# MCU063A_GPIO.net
KiCad netlist of a schematic drawn in Altium Designer
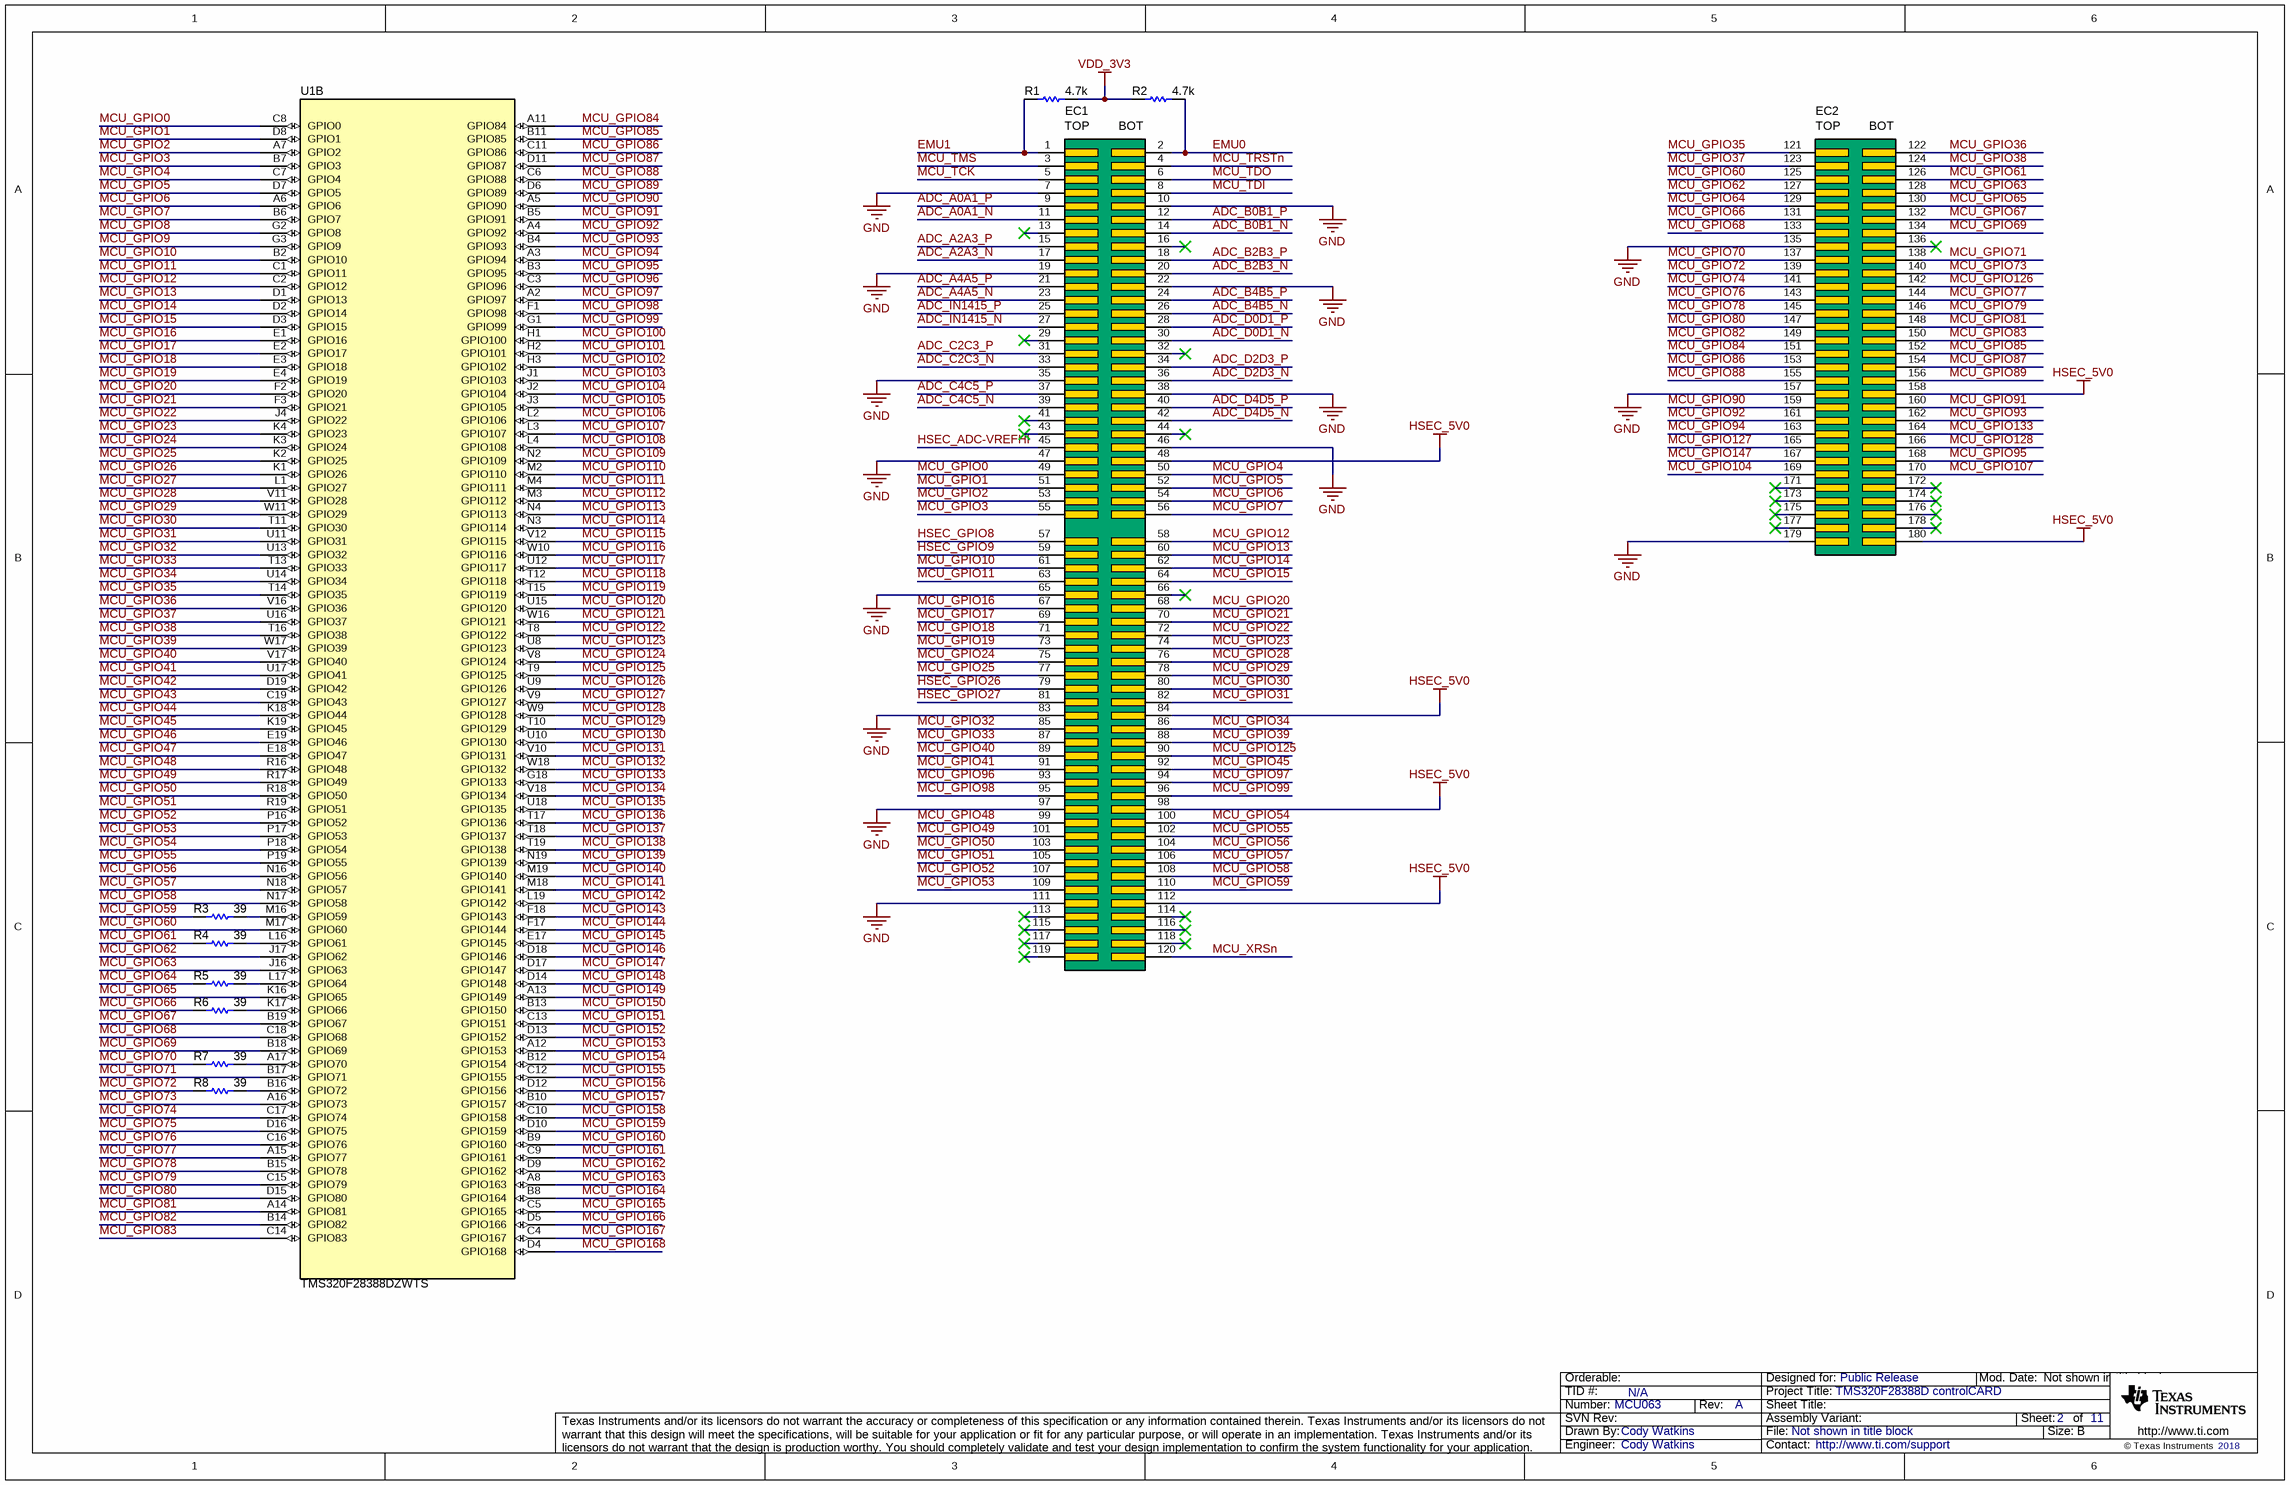
[diagram p0: MCU063A_GPIO.SchDoc]

(export (version "E")
  (design (tool "Eeschema 10.0.6"))
  (components
    (comp (ref "EC1")
      (value "controlCARD-120HSEC_Edge")
      (footprint "controlCARD-120HSEC_Edge")
      (description "C2000 controlCARD-120HSEC Edge Connector for Samtec HSEC8-160-01-L-DV-A-BL")
      (fields (field (name "MANUFACTURER") "Any"))
      (libsource (lib "Altium Vault - TI") (part "controlCARD-120HSEC_Edge"))
    )
    (comp (ref "EC2")
      (value "controlCARD-180HSEC-60pinAddon_Edge")
      (footprint "controlCARD-180HSEC-60pinAddon_Edge")
      (description "C2000 controlCARD-180HSEC (60-pin addon) Edge connector for Samtec HSEC8-130-01-L-DV-A")
      (fields (field (name "MANUFACTURER") "Any"))
      (libsource (lib "Altium Vault - TI") (part "controlCARD-180HSEC-60pinAddon_Edge"))
    )
    (comp (ref "R1")
      (value "CRCW04024K70JNED")
      (footprint "0402")
      (description "RES, 4.7 k, 5%, 0.063 W, AEC-Q200 Grade 0, 0402")
      (fields (field (name "MANUFACTURER") "Vishay-Dale") (field (name "VALUEDISPLAYED") "4.7k"))
      (libsource (lib "Altium Vault - TI") (part "Resistor"))
    )
    (comp (ref "R2")
      (value "CRCW04024K70JNED")
      (footprint "0402")
      (description "RES, 4.7 k, 5%, 0.063 W, AEC-Q200 Grade 0, 0402")
      (fields (field (name "MANUFACTURER") "Vishay-Dale") (field (name "VALUEDISPLAYED") "4.7k"))
      (libsource (lib "Altium Vault - TI") (part "Resistor"))
    )
    (comp (ref "R3")
      (value "CRCW040239R0JNED")
      (footprint "0402")
      (description "RES, 39, 5%, 0.063 W, AEC-Q200 Grade 0, 0402")
      (fields (field (name "MANUFACTURER") "Vishay-Dale") (field (name "VALUEDISPLAYED") "39"))
      (libsource (lib "Altium Vault - TI") (part "Resistor"))
    )
    (comp (ref "R4")
      (value "CRCW040239R0JNED")
      (footprint "0402")
      (description "RES, 39, 5%, 0.063 W, AEC-Q200 Grade 0, 0402")
      (fields (field (name "MANUFACTURER") "Vishay-Dale") (field (name "VALUEDISPLAYED") "39"))
      (libsource (lib "Altium Vault - TI") (part "Resistor"))
    )
    (comp (ref "R5")
      (value "CRCW040239R0JNED")
      (footprint "0402")
      (description "RES, 39, 5%, 0.063 W, AEC-Q200 Grade 0, 0402")
      (fields (field (name "MANUFACTURER") "Vishay-Dale") (field (name "VALUEDISPLAYED") "39"))
      (libsource (lib "Altium Vault - TI") (part "Resistor"))
    )
    (comp (ref "R6")
      (value "CRCW040239R0JNED")
      (footprint "0402")
      (description "RES, 39, 5%, 0.063 W, AEC-Q200 Grade 0, 0402")
      (fields (field (name "MANUFACTURER") "Vishay-Dale") (field (name "VALUEDISPLAYED") "39"))
      (libsource (lib "Altium Vault - TI") (part "Resistor"))
    )
    (comp (ref "R7")
      (value "CRCW040239R0JNED")
      (footprint "0402")
      (description "RES, 39, 5%, 0.063 W, AEC-Q200 Grade 0, 0402")
      (fields (field (name "MANUFACTURER") "Vishay-Dale") (field (name "VALUEDISPLAYED") "39"))
      (libsource (lib "Altium Vault - TI") (part "Resistor"))
    )
    (comp (ref "R8")
      (value "CRCW040239R0JNED")
      (footprint "0402")
      (description "RES, 39, 5%, 0.063 W, AEC-Q200 Grade 0, 0402")
      (fields (field (name "MANUFACTURER") "Vishay-Dale") (field (name "VALUEDISPLAYED") "39"))
      (libsource (lib "Altium Vault - TI") (part "Resistor"))
    )
    (comp (ref "U1")
      (value "TMS320F28388DZWTS")
      (footprint "ZWT0337A")
      (description "TMS320F28388DZWTS, ZWT0337A (NFBGA-337)")
      (fields
        (field (name "PARTNUMBER") "TMS320F28388DZWTS")
        (field (name "MANUFACTURER") "Texas Instruments")
      )
      (libsource (lib "Altium Vault - TI") (part "TMS320F28388"))
    )
  )
  (nets
    (net (code "1") (name "/ADC_A0A1_N") (class "Default")
      (node (ref "EC1") (pin "11") (pinfunction "11_11") (pintype "passive"))
    )
    (net (code "2") (name "/ADC_A0A1_P") (class "Default")
      (node (ref "EC1") (pin "9") (pinfunction "9_9") (pintype "passive"))
    )
    (net (code "3") (name "/ADC_A2A3_N") (class "Default")
      (node (ref "EC1") (pin "17") (pinfunction "17_17") (pintype "passive"))
    )
    (net (code "4") (name "/ADC_A2A3_P") (class "Default")
      (node (ref "EC1") (pin "15") (pinfunction "15_15") (pintype "passive"))
    )
    (net (code "5") (name "/ADC_A4A5_N") (class "Default")
      (node (ref "EC1") (pin "23") (pinfunction "23_23") (pintype "passive"))
    )
    (net (code "6") (name "/ADC_A4A5_P") (class "Default")
      (node (ref "EC1") (pin "21") (pinfunction "21_21") (pintype "passive"))
    )
    (net (code "7") (name "/ADC_B0B1_N") (class "Default")
      (node (ref "EC1") (pin "14") (pinfunction "14_14") (pintype "passive"))
    )
    (net (code "8") (name "/ADC_B0B1_P") (class "Default")
      (node (ref "EC1") (pin "12") (pinfunction "12_12") (pintype "passive"))
    )
    (net (code "9") (name "/ADC_B2B3_N") (class "Default")
      (node (ref "EC1") (pin "20") (pinfunction "20_20") (pintype "passive"))
    )
    (net (code "10") (name "/ADC_B2B3_P") (class "Default")
      (node (ref "EC1") (pin "18") (pinfunction "18_18") (pintype "passive"))
    )
    (net (code "11") (name "/ADC_B4B5_N") (class "Default")
      (node (ref "EC1") (pin "26") (pinfunction "26_26") (pintype "passive"))
    )
    (net (code "12") (name "/ADC_B4B5_P") (class "Default")
      (node (ref "EC1") (pin "24") (pinfunction "24_24") (pintype "passive"))
    )
    (net (code "13") (name "/ADC_C2C3_N") (class "Default")
      (node (ref "EC1") (pin "33") (pinfunction "33_33") (pintype "passive"))
    )
    (net (code "14") (name "/ADC_C2C3_P") (class "Default")
      (node (ref "EC1") (pin "31") (pinfunction "31_31") (pintype "passive"))
    )
    (net (code "15") (name "/ADC_C4C5_N") (class "Default")
      (node (ref "EC1") (pin "39") (pinfunction "39_39") (pintype "passive"))
    )
    (net (code "16") (name "/ADC_C4C5_P") (class "Default")
      (node (ref "EC1") (pin "37") (pinfunction "37_37") (pintype "passive"))
    )
    (net (code "17") (name "/ADC_D0D1_N") (class "Default")
      (node (ref "EC1") (pin "30") (pinfunction "30_30") (pintype "passive"))
    )
    (net (code "18") (name "/ADC_D0D1_P") (class "Default")
      (node (ref "EC1") (pin "28") (pinfunction "28_28") (pintype "passive"))
    )
    (net (code "19") (name "/ADC_D2D3_N") (class "Default")
      (node (ref "EC1") (pin "36") (pinfunction "36_36") (pintype "passive"))
    )
    (net (code "20") (name "/ADC_D2D3_P") (class "Default")
      (node (ref "EC1") (pin "34") (pinfunction "34_34") (pintype "passive"))
    )
    (net (code "21") (name "/ADC_D4D5_N") (class "Default")
      (node (ref "EC1") (pin "42") (pinfunction "42_42") (pintype "passive"))
    )
    (net (code "22") (name "/ADC_D4D5_P") (class "Default")
      (node (ref "EC1") (pin "40") (pinfunction "40_40") (pintype "passive"))
    )
    (net (code "23") (name "/ADC_IN1415_N") (class "Default")
      (node (ref "EC1") (pin "27") (pinfunction "27_27") (pintype "passive"))
    )
    (net (code "24") (name "/ADC_IN1415_P") (class "Default")
      (node (ref "EC1") (pin "25") (pinfunction "25_25") (pintype "passive"))
    )
    (net (code "25") (name "/EMU0") (class "Default")
      (node (ref "EC1") (pin "2") (pinfunction "2_2") (pintype "passive"))
      (node (ref "R2") (pin "2") (pinfunction "2_2") (pintype "passive"))
    )
    (net (code "26") (name "/EMU1") (class "Default")
      (node (ref "EC1") (pin "1") (pinfunction "1_1") (pintype "passive"))
      (node (ref "R1") (pin "1") (pinfunction "1_1") (pintype "passive"))
    )
    (net (code "27") (name "/HSEC_ADC-VREFHI") (class "Default")
      (node (ref "EC1") (pin "45") (pinfunction "45_45") (pintype "passive"))
    )
    (net (code "28") (name "/HSEC_GPIO8") (class "Default")
      (node (ref "EC1") (pin "57") (pinfunction "57_57") (pintype "passive"))
    )
    (net (code "29") (name "/HSEC_GPIO9") (class "Default")
      (node (ref "EC1") (pin "59") (pinfunction "59_59") (pintype "passive"))
    )
    (net (code "30") (name "/HSEC_GPIO26") (class "Default")
      (node (ref "EC1") (pin "79") (pinfunction "79_79") (pintype "passive"))
    )
    (net (code "31") (name "/HSEC_GPIO27") (class "Default")
      (node (ref "EC1") (pin "81") (pinfunction "81_81") (pintype "passive"))
    )
    (net (code "32") (name "/MCU_GPIO0") (class "Default")
      (node (ref "EC1") (pin "49") (pinfunction "49_49") (pintype "passive"))
      (node (ref "U1") (pin "C8") (pinfunction "GPIO0_C8") (pintype "bidirectional"))
    )
    (net (code "33") (name "/MCU_GPIO1") (class "Default")
      (node (ref "EC1") (pin "51") (pinfunction "51_51") (pintype "passive"))
      (node (ref "U1") (pin "D8") (pinfunction "GPIO1_D8") (pintype "bidirectional"))
    )
    (net (code "34") (name "/MCU_GPIO2") (class "Default")
      (node (ref "EC1") (pin "53") (pinfunction "53_53") (pintype "passive"))
      (node (ref "U1") (pin "A7") (pinfunction "GPIO2_A7") (pintype "bidirectional"))
    )
    (net (code "35") (name "/MCU_GPIO3") (class "Default")
      (node (ref "EC1") (pin "55") (pinfunction "55_55") (pintype "passive"))
      (node (ref "U1") (pin "B7") (pinfunction "GPIO3_B7") (pintype "bidirectional"))
    )
    (net (code "36") (name "/MCU_GPIO4") (class "Default")
      (node (ref "EC1") (pin "50") (pinfunction "50_50") (pintype "passive"))
      (node (ref "U1") (pin "C7") (pinfunction "GPIO4_C7") (pintype "bidirectional"))
    )
    (net (code "37") (name "/MCU_GPIO5") (class "Default")
      (node (ref "EC1") (pin "52") (pinfunction "52_52") (pintype "passive"))
      (node (ref "U1") (pin "D7") (pinfunction "GPIO5_D7") (pintype "bidirectional"))
    )
    (net (code "38") (name "/MCU_GPIO6") (class "Default")
      (node (ref "EC1") (pin "54") (pinfunction "54_54") (pintype "passive"))
      (node (ref "U1") (pin "A6") (pinfunction "GPIO6_A6") (pintype "bidirectional"))
    )
    (net (code "39") (name "/MCU_GPIO7") (class "Default")
      (node (ref "EC1") (pin "56") (pinfunction "56_56") (pintype "passive"))
      (node (ref "U1") (pin "B6") (pinfunction "GPIO7_B6") (pintype "bidirectional"))
    )
    (net (code "40") (name "/MCU_GPIO8") (class "Default")
      (node (ref "U1") (pin "G2") (pinfunction "GPIO8_G2") (pintype "bidirectional"))
    )
    (net (code "41") (name "/MCU_GPIO9") (class "Default")
      (node (ref "U1") (pin "G3") (pinfunction "GPIO9_G3") (pintype "bidirectional"))
    )
    (net (code "42") (name "/MCU_GPIO10") (class "Default")
      (node (ref "EC1") (pin "61") (pinfunction "61_61") (pintype "passive"))
      (node (ref "U1") (pin "B2") (pinfunction "GPIO10_B2") (pintype "bidirectional"))
    )
    (net (code "43") (name "/MCU_GPIO11") (class "Default")
      (node (ref "EC1") (pin "63") (pinfunction "63_63") (pintype "passive"))
      (node (ref "U1") (pin "C1") (pinfunction "GPIO11_C1") (pintype "bidirectional"))
    )
    (net (code "44") (name "/MCU_GPIO12") (class "Default")
      (node (ref "EC1") (pin "58") (pinfunction "58_58") (pintype "passive"))
      (node (ref "U1") (pin "C2") (pinfunction "GPIO12_C2") (pintype "bidirectional"))
    )
    (net (code "45") (name "/MCU_GPIO13") (class "Default")
      (node (ref "EC1") (pin "60") (pinfunction "60_60") (pintype "passive"))
      (node (ref "U1") (pin "D1") (pinfunction "GPIO13_D1") (pintype "bidirectional"))
    )
    (net (code "46") (name "/MCU_GPIO14") (class "Default")
      (node (ref "EC1") (pin "62") (pinfunction "62_62") (pintype "passive"))
      (node (ref "U1") (pin "D2") (pinfunction "GPIO14_D2") (pintype "bidirectional"))
    )
    (net (code "47") (name "/MCU_GPIO15") (class "Default")
      (node (ref "EC1") (pin "64") (pinfunction "64_64") (pintype "passive"))
      (node (ref "U1") (pin "D3") (pinfunction "GPIO15_D3") (pintype "bidirectional"))
    )
    (net (code "48") (name "/MCU_GPIO16") (class "Default")
      (node (ref "EC1") (pin "67") (pinfunction "67_67") (pintype "passive"))
      (node (ref "U1") (pin "E1") (pinfunction "GPIO16_E1") (pintype "bidirectional"))
    )
    (net (code "49") (name "/MCU_GPIO17") (class "Default")
      (node (ref "EC1") (pin "69") (pinfunction "69_69") (pintype "passive"))
      (node (ref "U1") (pin "E2") (pinfunction "GPIO17_E2") (pintype "bidirectional"))
    )
    (net (code "50") (name "/MCU_GPIO18") (class "Default")
      (node (ref "EC1") (pin "71") (pinfunction "71_71") (pintype "passive"))
      (node (ref "U1") (pin "E3") (pinfunction "GPIO18_E3") (pintype "bidirectional"))
    )
    (net (code "51") (name "/MCU_GPIO19") (class "Default")
      (node (ref "EC1") (pin "73") (pinfunction "73_73") (pintype "passive"))
      (node (ref "U1") (pin "E4") (pinfunction "GPIO19_E4") (pintype "bidirectional"))
    )
    (net (code "52") (name "/MCU_GPIO20") (class "Default")
      (node (ref "EC1") (pin "68") (pinfunction "68_68") (pintype "passive"))
      (node (ref "U1") (pin "F2") (pinfunction "GPIO20_F2") (pintype "bidirectional"))
    )
    (net (code "53") (name "/MCU_GPIO21") (class "Default")
      (node (ref "EC1") (pin "70") (pinfunction "70_70") (pintype "passive"))
      (node (ref "U1") (pin "F3") (pinfunction "GPIO21_F3") (pintype "bidirectional"))
    )
    (net (code "54") (name "/MCU_GPIO22") (class "Default")
      (node (ref "EC1") (pin "72") (pinfunction "72_72") (pintype "passive"))
      (node (ref "U1") (pin "J4") (pinfunction "GPIO22_J4") (pintype "bidirectional"))
    )
    (net (code "55") (name "/MCU_GPIO23") (class "Default")
      (node (ref "EC1") (pin "74") (pinfunction "74_74") (pintype "passive"))
      (node (ref "U1") (pin "K4") (pinfunction "GPIO23_K4") (pintype "bidirectional"))
    )
    (net (code "56") (name "/MCU_GPIO24") (class "Default")
      (node (ref "EC1") (pin "75") (pinfunction "75_75") (pintype "passive"))
      (node (ref "U1") (pin "K3") (pinfunction "GPIO24_K3") (pintype "bidirectional"))
    )
    (net (code "57") (name "/MCU_GPIO25") (class "Default")
      (node (ref "EC1") (pin "77") (pinfunction "77_77") (pintype "passive"))
      (node (ref "U1") (pin "K2") (pinfunction "GPIO25_K2") (pintype "bidirectional"))
    )
    (net (code "58") (name "/MCU_GPIO26") (class "Default")
      (node (ref "U1") (pin "K1") (pinfunction "GPIO26_K1") (pintype "bidirectional"))
    )
    (net (code "59") (name "/MCU_GPIO27") (class "Default")
      (node (ref "U1") (pin "L1") (pinfunction "GPIO27_L1") (pintype "bidirectional"))
    )
    (net (code "60") (name "/MCU_GPIO28") (class "Default")
      (node (ref "EC1") (pin "76") (pinfunction "76_76") (pintype "passive"))
      (node (ref "U1") (pin "V11") (pinfunction "GPIO28_V11") (pintype "bidirectional"))
    )
    (net (code "61") (name "/MCU_GPIO29") (class "Default")
      (node (ref "EC1") (pin "78") (pinfunction "78_78") (pintype "passive"))
      (node (ref "U1") (pin "W11") (pinfunction "GPIO29_W11") (pintype "bidirectional"))
    )
    (net (code "62") (name "/MCU_GPIO30") (class "Default")
      (node (ref "EC1") (pin "80") (pinfunction "80_80") (pintype "passive"))
      (node (ref "U1") (pin "T11") (pinfunction "GPIO30_T11") (pintype "bidirectional"))
    )
    (net (code "63") (name "/MCU_GPIO31") (class "Default")
      (node (ref "EC1") (pin "82") (pinfunction "82_82") (pintype "passive"))
      (node (ref "U1") (pin "U11") (pinfunction "GPIO31_U11") (pintype "bidirectional"))
    )
    (net (code "64") (name "/MCU_GPIO32") (class "Default")
      (node (ref "EC1") (pin "85") (pinfunction "85_85") (pintype "passive"))
      (node (ref "U1") (pin "U13") (pinfunction "GPIO32_U13") (pintype "bidirectional"))
    )
    (net (code "65") (name "/MCU_GPIO33") (class "Default")
      (node (ref "EC1") (pin "87") (pinfunction "87_87") (pintype "passive"))
      (node (ref "U1") (pin "T13") (pinfunction "GPIO33_T13") (pintype "bidirectional"))
    )
    (net (code "66") (name "/MCU_GPIO34") (class "Default")
      (node (ref "EC1") (pin "86") (pinfunction "86_86") (pintype "passive"))
      (node (ref "U1") (pin "U14") (pinfunction "GPIO34_U14") (pintype "bidirectional"))
    )
    (net (code "67") (name "/MCU_GPIO35") (class "Default")
      (node (ref "EC2") (pin "121") (pinfunction "121_121") (pintype "passive"))
      (node (ref "U1") (pin "T14") (pinfunction "GPIO35_T14") (pintype "bidirectional"))
    )
    (net (code "68") (name "/MCU_GPIO36") (class "Default")
      (node (ref "EC2") (pin "122") (pinfunction "122_122") (pintype "passive"))
      (node (ref "U1") (pin "V16") (pinfunction "GPIO36_V16") (pintype "bidirectional"))
    )
    (net (code "69") (name "/MCU_GPIO37") (class "Default")
      (node (ref "EC2") (pin "123") (pinfunction "123_123") (pintype "passive"))
      (node (ref "U1") (pin "U16") (pinfunction "GPIO37_U16") (pintype "bidirectional"))
    )
    (net (code "70") (name "/MCU_GPIO38") (class "Default")
      (node (ref "EC2") (pin "124") (pinfunction "124_124") (pintype "passive"))
      (node (ref "U1") (pin "T16") (pinfunction "GPIO38_T16") (pintype "bidirectional"))
    )
    (net (code "71") (name "/MCU_GPIO39") (class "Default")
      (node (ref "EC1") (pin "88") (pinfunction "88_88") (pintype "passive"))
      (node (ref "U1") (pin "W17") (pinfunction "GPIO39_W17") (pintype "bidirectional"))
    )
    (net (code "72") (name "/MCU_GPIO40") (class "Default")
      (node (ref "EC1") (pin "89") (pinfunction "89_89") (pintype "passive"))
      (node (ref "U1") (pin "V17") (pinfunction "GPIO40_V17") (pintype "bidirectional"))
    )
    (net (code "73") (name "/MCU_GPIO41") (class "Default")
      (node (ref "EC1") (pin "91") (pinfunction "91_91") (pintype "passive"))
      (node (ref "U1") (pin "U17") (pinfunction "GPIO41_U17") (pintype "bidirectional"))
    )
    (net (code "74") (name "/MCU_GPIO42") (class "Default")
      (node (ref "U1") (pin "D19") (pinfunction "GPIO42_D19") (pintype "bidirectional"))
    )
    (net (code "75") (name "/MCU_GPIO43") (class "Default")
      (node (ref "U1") (pin "C19") (pinfunction "GPIO43_C19") (pintype "bidirectional"))
    )
    (net (code "76") (name "/MCU_GPIO44") (class "Default")
      (node (ref "U1") (pin "K18") (pinfunction "GPIO44_K18") (pintype "bidirectional"))
    )
    (net (code "77") (name "/MCU_GPIO45") (class "Default")
      (node (ref "EC1") (pin "92") (pinfunction "92_92") (pintype "passive"))
      (node (ref "U1") (pin "K19") (pinfunction "GPIO45_K19") (pintype "bidirectional"))
    )
    (net (code "78") (name "/MCU_GPIO46") (class "Default")
      (node (ref "U1") (pin "E19") (pinfunction "GPIO46_E19") (pintype "bidirectional"))
    )
    (net (code "79") (name "/MCU_GPIO47") (class "Default")
      (node (ref "U1") (pin "E18") (pinfunction "GPIO47_E18") (pintype "bidirectional"))
    )
    (net (code "80") (name "/MCU_GPIO48") (class "Default")
      (node (ref "EC1") (pin "99") (pinfunction "99_99") (pintype "passive"))
      (node (ref "U1") (pin "R16") (pinfunction "GPIO48_R16") (pintype "bidirectional"))
    )
    (net (code "81") (name "/MCU_GPIO49") (class "Default")
      (node (ref "EC1") (pin "101") (pinfunction "101_101") (pintype "passive"))
      (node (ref "U1") (pin "R17") (pinfunction "GPIO49_R17") (pintype "bidirectional"))
    )
    (net (code "82") (name "/MCU_GPIO50") (class "Default")
      (node (ref "EC1") (pin "103") (pinfunction "103_103") (pintype "passive"))
      (node (ref "U1") (pin "R18") (pinfunction "GPIO50_R18") (pintype "bidirectional"))
    )
    (net (code "83") (name "/MCU_GPIO51") (class "Default")
      (node (ref "EC1") (pin "105") (pinfunction "105_105") (pintype "passive"))
      (node (ref "U1") (pin "R19") (pinfunction "GPIO51_R19") (pintype "bidirectional"))
    )
    (net (code "84") (name "/MCU_GPIO52") (class "Default")
      (node (ref "EC1") (pin "107") (pinfunction "107_107") (pintype "passive"))
      (node (ref "U1") (pin "P16") (pinfunction "GPIO52_P16") (pintype "bidirectional"))
    )
    (net (code "85") (name "/MCU_GPIO53") (class "Default")
      (node (ref "EC1") (pin "109") (pinfunction "109_109") (pintype "passive"))
      (node (ref "U1") (pin "P17") (pinfunction "GPIO53_P17") (pintype "bidirectional"))
    )
    (net (code "86") (name "/MCU_GPIO54") (class "Default")
      (node (ref "EC1") (pin "100") (pinfunction "100_100") (pintype "passive"))
      (node (ref "U1") (pin "P18") (pinfunction "GPIO54_P18") (pintype "bidirectional"))
    )
    (net (code "87") (name "/MCU_GPIO55") (class "Default")
      (node (ref "EC1") (pin "102") (pinfunction "102_102") (pintype "passive"))
      (node (ref "U1") (pin "P19") (pinfunction "GPIO55_P19") (pintype "bidirectional"))
    )
    (net (code "88") (name "/MCU_GPIO56") (class "Default")
      (node (ref "EC1") (pin "104") (pinfunction "104_104") (pintype "passive"))
      (node (ref "U1") (pin "N16") (pinfunction "GPIO56_N16") (pintype "bidirectional"))
    )
    (net (code "89") (name "/MCU_GPIO57") (class "Default")
      (node (ref "EC1") (pin "106") (pinfunction "106_106") (pintype "passive"))
      (node (ref "U1") (pin "N18") (pinfunction "GPIO57_N18") (pintype "bidirectional"))
    )
    (net (code "90") (name "/MCU_GPIO58") (class "Default")
      (node (ref "EC1") (pin "108") (pinfunction "108_108") (pintype "passive"))
      (node (ref "U1") (pin "N17") (pinfunction "GPIO58_N17") (pintype "bidirectional"))
    )
    (net (code "91") (name "/MCU_GPIO59") (class "Default")
      (node (ref "EC1") (pin "110") (pinfunction "110_110") (pintype "passive"))
      (node (ref "R3") (pin "1") (pinfunction "1_1") (pintype "passive"))
    )
    (net (code "92") (name "/MCU_GPIO60") (class "Default")
      (node (ref "EC2") (pin "125") (pinfunction "125_125") (pintype "passive"))
      (node (ref "U1") (pin "M17") (pinfunction "GPIO60_M17") (pintype "bidirectional"))
    )
    (net (code "93") (name "/MCU_GPIO61") (class "Default")
      (node (ref "EC2") (pin "126") (pinfunction "126_126") (pintype "passive"))
      (node (ref "R4") (pin "1") (pinfunction "1_1") (pintype "passive"))
    )
    (net (code "94") (name "/MCU_GPIO62") (class "Default")
      (node (ref "EC2") (pin "127") (pinfunction "127_127") (pintype "passive"))
      (node (ref "U1") (pin "J17") (pinfunction "GPIO62_J17") (pintype "bidirectional"))
    )
    (net (code "95") (name "/MCU_GPIO63") (class "Default")
      (node (ref "EC2") (pin "128") (pinfunction "128_128") (pintype "passive"))
      (node (ref "U1") (pin "J16") (pinfunction "GPIO63_J16") (pintype "bidirectional"))
    )
    (net (code "96") (name "/MCU_GPIO64") (class "Default")
      (node (ref "EC2") (pin "129") (pinfunction "129_129") (pintype "passive"))
      (node (ref "R5") (pin "1") (pinfunction "1_1") (pintype "passive"))
    )
    (net (code "97") (name "/MCU_GPIO65") (class "Default")
      (node (ref "EC2") (pin "130") (pinfunction "130_130") (pintype "passive"))
      (node (ref "U1") (pin "K16") (pinfunction "GPIO65_K16") (pintype "bidirectional"))
    )
    (net (code "98") (name "/MCU_GPIO66") (class "Default")
      (node (ref "EC2") (pin "131") (pinfunction "131_131") (pintype "passive"))
      (node (ref "R6") (pin "1") (pinfunction "1_1") (pintype "passive"))
    )
    (net (code "99") (name "/MCU_GPIO67") (class "Default")
      (node (ref "EC2") (pin "132") (pinfunction "132_132") (pintype "passive"))
      (node (ref "U1") (pin "B19") (pinfunction "GPIO67_B19") (pintype "bidirectional"))
    )
    (net (code "100") (name "/MCU_GPIO68") (class "Default")
      (node (ref "EC2") (pin "133") (pinfunction "133_133") (pintype "passive"))
      (node (ref "U1") (pin "C18") (pinfunction "GPIO68_C18") (pintype "bidirectional"))
    )
    (net (code "101") (name "/MCU_GPIO69") (class "Default")
      (node (ref "EC2") (pin "134") (pinfunction "134_134") (pintype "passive"))
      (node (ref "U1") (pin "B18") (pinfunction "GPIO69_B18") (pintype "bidirectional"))
    )
    (net (code "102") (name "/MCU_GPIO70") (class "Default")
      (node (ref "EC2") (pin "137") (pinfunction "137_137") (pintype "passive"))
      (node (ref "R7") (pin "1") (pinfunction "1_1") (pintype "passive"))
    )
    (net (code "103") (name "/MCU_GPIO71") (class "Default")
      (node (ref "EC2") (pin "138") (pinfunction "138_138") (pintype "passive"))
      (node (ref "U1") (pin "B17") (pinfunction "GPIO71_B17") (pintype "bidirectional"))
    )
    (net (code "104") (name "/MCU_GPIO72") (class "Default")
      (node (ref "EC2") (pin "139") (pinfunction "139_139") (pintype "passive"))
      (node (ref "R8") (pin "1") (pinfunction "1_1") (pintype "passive"))
    )
    (net (code "105") (name "/MCU_GPIO73") (class "Default")
      (node (ref "EC2") (pin "140") (pinfunction "140_140") (pintype "passive"))
      (node (ref "U1") (pin "A16") (pinfunction "GPIO73_A16") (pintype "bidirectional"))
    )
    (net (code "106") (name "/MCU_GPIO74") (class "Default")
      (node (ref "EC2") (pin "141") (pinfunction "141_141") (pintype "passive"))
      (node (ref "U1") (pin "C17") (pinfunction "GPIO74_C17") (pintype "bidirectional"))
    )
    (net (code "107") (name "/MCU_GPIO75") (class "Default")
      (node (ref "U1") (pin "D16") (pinfunction "GPIO75_D16") (pintype "bidirectional"))
    )
    (net (code "108") (name "/MCU_GPIO76") (class "Default")
      (node (ref "EC2") (pin "143") (pinfunction "143_143") (pintype "passive"))
      (node (ref "U1") (pin "C16") (pinfunction "GPIO76_C16") (pintype "bidirectional"))
    )
    (net (code "109") (name "/MCU_GPIO77") (class "Default")
      (node (ref "EC2") (pin "144") (pinfunction "144_144") (pintype "passive"))
      (node (ref "U1") (pin "A15") (pinfunction "GPIO77_A15") (pintype "bidirectional"))
    )
    (net (code "110") (name "/MCU_GPIO78") (class "Default")
      (node (ref "EC2") (pin "145") (pinfunction "145_145") (pintype "passive"))
      (node (ref "U1") (pin "B15") (pinfunction "GPIO78_B15") (pintype "bidirectional"))
    )
    (net (code "111") (name "/MCU_GPIO79") (class "Default")
      (node (ref "EC2") (pin "146") (pinfunction "146_146") (pintype "passive"))
      (node (ref "U1") (pin "C15") (pinfunction "GPIO79_C15") (pintype "bidirectional"))
    )
    (net (code "112") (name "/MCU_GPIO80") (class "Default")
      (node (ref "EC2") (pin "147") (pinfunction "147_147") (pintype "passive"))
      (node (ref "U1") (pin "D15") (pinfunction "GPIO80_D15") (pintype "bidirectional"))
    )
    (net (code "113") (name "/MCU_GPIO81") (class "Default")
      (node (ref "EC2") (pin "148") (pinfunction "148_148") (pintype "passive"))
      (node (ref "U1") (pin "A14") (pinfunction "GPIO81_A14") (pintype "bidirectional"))
    )
    (net (code "114") (name "/MCU_GPIO82") (class "Default")
      (node (ref "EC2") (pin "149") (pinfunction "149_149") (pintype "passive"))
      (node (ref "U1") (pin "B14") (pinfunction "GPIO82_B14") (pintype "bidirectional"))
    )
    (net (code "115") (name "/MCU_GPIO83") (class "Default")
      (node (ref "EC2") (pin "150") (pinfunction "150_150") (pintype "passive"))
      (node (ref "U1") (pin "C14") (pinfunction "GPIO83_C14") (pintype "bidirectional"))
    )
    (net (code "116") (name "/MCU_GPIO84") (class "Default")
      (node (ref "EC2") (pin "151") (pinfunction "151_151") (pintype "passive"))
      (node (ref "U1") (pin "A11") (pinfunction "GPIO84_A11") (pintype "bidirectional"))
    )
    (net (code "117") (name "/MCU_GPIO85") (class "Default")
      (node (ref "EC2") (pin "152") (pinfunction "152_152") (pintype "passive"))
      (node (ref "U1") (pin "B11") (pinfunction "GPIO85_B11") (pintype "bidirectional"))
    )
    (net (code "118") (name "/MCU_GPIO86") (class "Default")
      (node (ref "EC2") (pin "153") (pinfunction "153_153") (pintype "passive"))
      (node (ref "U1") (pin "C11") (pinfunction "GPIO86_C11") (pintype "bidirectional"))
    )
    (net (code "119") (name "/MCU_GPIO87") (class "Default")
      (node (ref "EC2") (pin "154") (pinfunction "154_154") (pintype "passive"))
      (node (ref "U1") (pin "D11") (pinfunction "GPIO87_D11") (pintype "bidirectional"))
    )
    (net (code "120") (name "/MCU_GPIO88") (class "Default")
      (node (ref "EC2") (pin "155") (pinfunction "155_155") (pintype "passive"))
      (node (ref "U1") (pin "C6") (pinfunction "GPIO88_C6") (pintype "bidirectional"))
    )
    (net (code "121") (name "/MCU_GPIO89") (class "Default")
      (node (ref "EC2") (pin "156") (pinfunction "156_156") (pintype "passive"))
      (node (ref "U1") (pin "D6") (pinfunction "GPIO89_D6") (pintype "bidirectional"))
    )
    (net (code "122") (name "/MCU_GPIO90") (class "Default")
      (node (ref "EC2") (pin "159") (pinfunction "159_159") (pintype "passive"))
      (node (ref "U1") (pin "A5") (pinfunction "GPIO90_A5") (pintype "bidirectional"))
    )
    (net (code "123") (name "/MCU_GPIO91") (class "Default")
      (node (ref "EC2") (pin "160") (pinfunction "160_160") (pintype "passive"))
      (node (ref "U1") (pin "B5") (pinfunction "GPIO91_B5") (pintype "bidirectional"))
    )
    (net (code "124") (name "/MCU_GPIO92") (class "Default")
      (node (ref "EC2") (pin "161") (pinfunction "161_161") (pintype "passive"))
      (node (ref "U1") (pin "A4") (pinfunction "GPIO92_A4") (pintype "bidirectional"))
    )
    (net (code "125") (name "/MCU_GPIO93") (class "Default")
      (node (ref "EC2") (pin "162") (pinfunction "162_162") (pintype "passive"))
      (node (ref "U1") (pin "B4") (pinfunction "GPIO93_B4") (pintype "bidirectional"))
    )
    (net (code "126") (name "/MCU_GPIO94") (class "Default")
      (node (ref "EC2") (pin "163") (pinfunction "163_163") (pintype "passive"))
      (node (ref "U1") (pin "A3") (pinfunction "GPIO94_A3") (pintype "bidirectional"))
    )
    (net (code "127") (name "/MCU_GPIO95") (class "Default")
      (node (ref "EC2") (pin "168") (pinfunction "168_168") (pintype "passive"))
      (node (ref "U1") (pin "B3") (pinfunction "GPIO95_B3") (pintype "bidirectional"))
    )
    (net (code "128") (name "/MCU_GPIO96") (class "Default")
      (node (ref "EC1") (pin "93") (pinfunction "93_93") (pintype "passive"))
      (node (ref "U1") (pin "C3") (pinfunction "GPIO96_C3") (pintype "bidirectional"))
    )
    (net (code "129") (name "/MCU_GPIO97") (class "Default")
      (node (ref "EC1") (pin "94") (pinfunction "94_94") (pintype "passive"))
      (node (ref "U1") (pin "A2") (pinfunction "GPIO97_A2") (pintype "bidirectional"))
    )
    (net (code "130") (name "/MCU_GPIO98") (class "Default")
      (node (ref "EC1") (pin "95") (pinfunction "95_95") (pintype "passive"))
      (node (ref "U1") (pin "F1") (pinfunction "GPIO98_F1") (pintype "bidirectional"))
    )
    (net (code "131") (name "/MCU_GPIO99") (class "Default")
      (node (ref "EC1") (pin "96") (pinfunction "96_96") (pintype "passive"))
      (node (ref "U1") (pin "G1") (pinfunction "GPIO99_G1") (pintype "bidirectional"))
    )
    (net (code "132") (name "/MCU_GPIO100") (class "Default")
      (node (ref "U1") (pin "H1") (pinfunction "GPIO100_H1") (pintype "bidirectional"))
    )
    (net (code "133") (name "/MCU_GPIO101") (class "Default")
      (node (ref "U1") (pin "H2") (pinfunction "GPIO101_H2") (pintype "bidirectional"))
    )
    (net (code "134") (name "/MCU_GPIO102") (class "Default")
      (node (ref "U1") (pin "H3") (pinfunction "GPIO102_H3") (pintype "bidirectional"))
    )
    (net (code "135") (name "/MCU_GPIO103") (class "Default")
      (node (ref "U1") (pin "J1") (pinfunction "GPIO103_J1") (pintype "bidirectional"))
    )
    (net (code "136") (name "/MCU_GPIO104") (class "Default")
      (node (ref "EC2") (pin "169") (pinfunction "169_169") (pintype "passive"))
      (node (ref "U1") (pin "J2") (pinfunction "GPIO104_J2") (pintype "bidirectional"))
    )
    (net (code "137") (name "/MCU_GPIO105") (class "Default")
      (node (ref "U1") (pin "J3") (pinfunction "GPIO105_J3") (pintype "bidirectional"))
    )
    (net (code "138") (name "/MCU_GPIO106") (class "Default")
      (node (ref "U1") (pin "L2") (pinfunction "GPIO106_L2") (pintype "bidirectional"))
    )
    (net (code "139") (name "/MCU_GPIO107") (class "Default")
      (node (ref "EC2") (pin "170") (pinfunction "170_170") (pintype "passive"))
      (node (ref "U1") (pin "L3") (pinfunction "GPIO107_L3") (pintype "bidirectional"))
    )
    (net (code "140") (name "/MCU_GPIO108") (class "Default")
      (node (ref "U1") (pin "L4") (pinfunction "GPIO108_L4") (pintype "bidirectional"))
    )
    (net (code "141") (name "/MCU_GPIO109") (class "Default")
      (node (ref "U1") (pin "N2") (pinfunction "GPIO109_N2") (pintype "bidirectional"))
    )
    (net (code "142") (name "/MCU_GPIO110") (class "Default")
      (node (ref "U1") (pin "M2") (pinfunction "GPIO110_M2") (pintype "bidirectional"))
    )
    (net (code "143") (name "/MCU_GPIO111") (class "Default")
      (node (ref "U1") (pin "M4") (pinfunction "GPIO111_M4") (pintype "bidirectional"))
    )
    (net (code "144") (name "/MCU_GPIO112") (class "Default")
      (node (ref "U1") (pin "M3") (pinfunction "GPIO112_M3") (pintype "bidirectional"))
    )
    (net (code "145") (name "/MCU_GPIO113") (class "Default")
      (node (ref "U1") (pin "N4") (pinfunction "GPIO113_N4") (pintype "bidirectional"))
    )
    (net (code "146") (name "/MCU_GPIO114") (class "Default")
      (node (ref "U1") (pin "N3") (pinfunction "GPIO114_N3") (pintype "bidirectional"))
    )
    (net (code "147") (name "/MCU_GPIO115") (class "Default")
      (node (ref "U1") (pin "V12") (pinfunction "GPIO115_V12") (pintype "bidirectional"))
    )
    (net (code "148") (name "/MCU_GPIO116") (class "Default")
      (node (ref "U1") (pin "W10") (pinfunction "GPIO116_W10") (pintype "bidirectional"))
    )
    (net (code "149") (name "/MCU_GPIO117") (class "Default")
      (node (ref "U1") (pin "U12") (pinfunction "GPIO117_U12") (pintype "bidirectional"))
    )
    (net (code "150") (name "/MCU_GPIO118") (class "Default")
      (node (ref "U1") (pin "T12") (pinfunction "GPIO118_T12") (pintype "bidirectional"))
    )
    (net (code "151") (name "/MCU_GPIO119") (class "Default")
      (node (ref "U1") (pin "T15") (pinfunction "GPIO119_T15") (pintype "bidirectional"))
    )
    (net (code "152") (name "/MCU_GPIO120") (class "Default")
      (node (ref "U1") (pin "U15") (pinfunction "GPIO120_U15") (pintype "bidirectional"))
    )
    (net (code "153") (name "/MCU_GPIO121") (class "Default")
      (node (ref "U1") (pin "W16") (pinfunction "GPIO121_W16") (pintype "bidirectional"))
    )
    (net (code "154") (name "/MCU_GPIO122") (class "Default")
      (node (ref "U1") (pin "T8") (pinfunction "GPIO122_T8") (pintype "bidirectional"))
    )
    (net (code "155") (name "/MCU_GPIO123") (class "Default")
      (node (ref "U1") (pin "U8") (pinfunction "GPIO123_U8") (pintype "bidirectional"))
    )
    (net (code "156") (name "/MCU_GPIO124") (class "Default")
      (node (ref "U1") (pin "V8") (pinfunction "GPIO124_V8") (pintype "bidirectional"))
    )
    (net (code "157") (name "/MCU_GPIO125") (class "Default")
      (node (ref "EC1") (pin "90") (pinfunction "90_90") (pintype "passive"))
      (node (ref "U1") (pin "T9") (pinfunction "GPIO125_T9") (pintype "bidirectional"))
    )
    (net (code "158") (name "/MCU_GPIO126") (class "Default")
      (node (ref "EC2") (pin "142") (pinfunction "142_142") (pintype "passive"))
      (node (ref "U1") (pin "U9") (pinfunction "GPIO126_U9") (pintype "bidirectional"))
    )
    (net (code "159") (name "/MCU_GPIO127") (class "Default")
      (node (ref "EC2") (pin "165") (pinfunction "165_165") (pintype "passive"))
      (node (ref "U1") (pin "V9") (pinfunction "GPIO127_V9") (pintype "bidirectional"))
    )
    (net (code "160") (name "/MCU_GPIO128") (class "Default")
      (node (ref "EC2") (pin "166") (pinfunction "166_166") (pintype "passive"))
      (node (ref "U1") (pin "W9") (pinfunction "GPIO128_W9") (pintype "bidirectional"))
    )
    (net (code "161") (name "/MCU_GPIO129") (class "Default")
      (node (ref "U1") (pin "T10") (pinfunction "GPIO129_T10") (pintype "bidirectional"))
    )
    (net (code "162") (name "/MCU_GPIO130") (class "Default")
      (node (ref "U1") (pin "U10") (pinfunction "GPIO130_U10") (pintype "bidirectional"))
    )
    (net (code "163") (name "/MCU_GPIO131") (class "Default")
      (node (ref "U1") (pin "V10") (pinfunction "GPIO131_V10") (pintype "bidirectional"))
    )
    (net (code "164") (name "/MCU_GPIO132") (class "Default")
      (node (ref "U1") (pin "W18") (pinfunction "GPIO132_W18") (pintype "bidirectional"))
    )
    (net (code "165") (name "/MCU_GPIO133") (class "Default")
      (node (ref "EC2") (pin "164") (pinfunction "164_164") (pintype "passive"))
      (node (ref "U1") (pin "G18") (pinfunction "GPIO133_G18") (pintype "bidirectional"))
    )
    (net (code "166") (name "/MCU_GPIO134") (class "Default")
      (node (ref "U1") (pin "V18") (pinfunction "GPIO134_V18") (pintype "bidirectional"))
    )
    (net (code "167") (name "/MCU_GPIO135") (class "Default")
      (node (ref "U1") (pin "U18") (pinfunction "GPIO135_U18") (pintype "bidirectional"))
    )
    (net (code "168") (name "/MCU_GPIO136") (class "Default")
      (node (ref "U1") (pin "T17") (pinfunction "GPIO136_T17") (pintype "bidirectional"))
    )
    (net (code "169") (name "/MCU_GPIO137") (class "Default")
      (node (ref "U1") (pin "T18") (pinfunction "GPIO137_T18") (pintype "bidirectional"))
    )
    (net (code "170") (name "/MCU_GPIO138") (class "Default")
      (node (ref "U1") (pin "T19") (pinfunction "GPIO138_T19") (pintype "bidirectional"))
    )
    (net (code "171") (name "/MCU_GPIO139") (class "Default")
      (node (ref "U1") (pin "N19") (pinfunction "GPIO139_N19") (pintype "bidirectional"))
    )
    (net (code "172") (name "/MCU_GPIO140") (class "Default")
      (node (ref "U1") (pin "M19") (pinfunction "GPIO140_M19") (pintype "bidirectional"))
    )
    (net (code "173") (name "/MCU_GPIO141") (class "Default")
      (node (ref "U1") (pin "M18") (pinfunction "GPIO141_M18") (pintype "bidirectional"))
    )
    (net (code "174") (name "/MCU_GPIO142") (class "Default")
      (node (ref "U1") (pin "L19") (pinfunction "GPIO142_L19") (pintype "bidirectional"))
    )
    (net (code "175") (name "/MCU_GPIO143") (class "Default")
      (node (ref "U1") (pin "F18") (pinfunction "GPIO143_F18") (pintype "bidirectional"))
    )
    (net (code "176") (name "/MCU_GPIO144") (class "Default")
      (node (ref "U1") (pin "F17") (pinfunction "GPIO144_F17") (pintype "bidirectional"))
    )
    (net (code "177") (name "/MCU_GPIO145") (class "Default")
      (node (ref "U1") (pin "E17") (pinfunction "GPIO145_E17") (pintype "bidirectional"))
    )
    (net (code "178") (name "/MCU_GPIO146") (class "Default")
      (node (ref "U1") (pin "D18") (pinfunction "GPIO146_D18") (pintype "bidirectional"))
    )
    (net (code "179") (name "/MCU_GPIO147") (class "Default")
      (node (ref "EC2") (pin "167") (pinfunction "167_167") (pintype "passive"))
      (node (ref "U1") (pin "D17") (pinfunction "GPIO147_D17") (pintype "bidirectional"))
    )
    (net (code "180") (name "/MCU_GPIO148") (class "Default")
      (node (ref "U1") (pin "D14") (pinfunction "GPIO148_D14") (pintype "bidirectional"))
    )
    (net (code "181") (name "/MCU_GPIO149") (class "Default")
      (node (ref "U1") (pin "A13") (pinfunction "GPIO149_A13") (pintype "bidirectional"))
    )
    (net (code "182") (name "/MCU_GPIO150") (class "Default")
      (node (ref "U1") (pin "B13") (pinfunction "GPIO150_B13") (pintype "bidirectional"))
    )
    (net (code "183") (name "/MCU_GPIO151") (class "Default")
      (node (ref "U1") (pin "C13") (pinfunction "GPIO151_C13") (pintype "bidirectional"))
    )
    (net (code "184") (name "/MCU_GPIO152") (class "Default")
      (node (ref "U1") (pin "D13") (pinfunction "GPIO152_D13") (pintype "bidirectional"))
    )
    (net (code "185") (name "/MCU_GPIO153") (class "Default")
      (node (ref "U1") (pin "A12") (pinfunction "GPIO153_A12") (pintype "bidirectional"))
    )
    (net (code "186") (name "/MCU_GPIO154") (class "Default")
      (node (ref "U1") (pin "B12") (pinfunction "GPIO154_B12") (pintype "bidirectional"))
    )
    (net (code "187") (name "/MCU_GPIO155") (class "Default")
      (node (ref "U1") (pin "C12") (pinfunction "GPIO155_C12") (pintype "bidirectional"))
    )
    (net (code "188") (name "/MCU_GPIO156") (class "Default")
      (node (ref "U1") (pin "D12") (pinfunction "GPIO156_D12") (pintype "bidirectional"))
    )
    (net (code "189") (name "/MCU_GPIO157") (class "Default")
      (node (ref "U1") (pin "B10") (pinfunction "GPIO157_B10") (pintype "bidirectional"))
    )
    (net (code "190") (name "/MCU_GPIO158") (class "Default")
      (node (ref "U1") (pin "C10") (pinfunction "GPIO158_C10") (pintype "bidirectional"))
    )
    (net (code "191") (name "/MCU_GPIO159") (class "Default")
      (node (ref "U1") (pin "D10") (pinfunction "GPIO159_D10") (pintype "bidirectional"))
    )
    (net (code "192") (name "/MCU_GPIO160") (class "Default")
      (node (ref "U1") (pin "B9") (pinfunction "GPIO160_B9") (pintype "bidirectional"))
    )
    (net (code "193") (name "/MCU_GPIO161") (class "Default")
      (node (ref "U1") (pin "C9") (pinfunction "GPIO161_C9") (pintype "bidirectional"))
    )
    (net (code "194") (name "/MCU_GPIO162") (class "Default")
      (node (ref "U1") (pin "D9") (pinfunction "GPIO162_D9") (pintype "bidirectional"))
    )
    (net (code "195") (name "/MCU_GPIO163") (class "Default")
      (node (ref "U1") (pin "A8") (pinfunction "GPIO163_A8") (pintype "bidirectional"))
    )
    (net (code "196") (name "/MCU_GPIO164") (class "Default")
      (node (ref "U1") (pin "B8") (pinfunction "GPIO164_B8") (pintype "bidirectional"))
    )
    (net (code "197") (name "/MCU_GPIO165") (class "Default")
      (node (ref "U1") (pin "C5") (pinfunction "GPIO165_C5") (pintype "bidirectional"))
    )
    (net (code "198") (name "/MCU_GPIO166") (class "Default")
      (node (ref "U1") (pin "D5") (pinfunction "GPIO166_D5") (pintype "bidirectional"))
    )
    (net (code "199") (name "/MCU_GPIO167") (class "Default")
      (node (ref "U1") (pin "C4") (pinfunction "GPIO167_C4") (pintype "bidirectional"))
    )
    (net (code "200") (name "/MCU_GPIO168") (class "Default")
      (node (ref "U1") (pin "D4") (pinfunction "GPIO168_D4") (pintype "bidirectional"))
    )
    (net (code "201") (name "/MCU_TCK") (class "Default")
      (node (ref "EC1") (pin "5") (pinfunction "5_5") (pintype "passive"))
    )
    (net (code "202") (name "/MCU_TDI") (class "Default")
      (node (ref "EC1") (pin "8") (pinfunction "8_8") (pintype "passive"))
    )
    (net (code "203") (name "/MCU_TDO") (class "Default")
      (node (ref "EC1") (pin "6") (pinfunction "6_6") (pintype "passive"))
    )
    (net (code "204") (name "/MCU_TMS") (class "Default")
      (node (ref "EC1") (pin "3") (pinfunction "3_3") (pintype "passive"))
    )
    (net (code "205") (name "/MCU_TRSTn") (class "Default")
      (node (ref "EC1") (pin "4") (pinfunction "4_4") (pintype "passive"))
    )
    (net (code "206") (name "/MCU_XRSn") (class "Default")
      (node (ref "EC1") (pin "120") (pinfunction "120_120") (pintype "passive"))
    )
    (net (code "207") (name "GND") (class "Default")
      (node (ref "EC1") (pin "10") (pinfunction "10_10") (pintype "passive"))
      (node (ref "EC1") (pin "111") (pinfunction "111_111") (pintype "passive"))
      (node (ref "EC1") (pin "19") (pinfunction "19_19") (pintype "passive"))
      (node (ref "EC1") (pin "22") (pinfunction "22_22") (pintype "passive"))
      (node (ref "EC1") (pin "35") (pinfunction "35_35") (pintype "passive"))
      (node (ref "EC1") (pin "38") (pinfunction "38_38") (pintype "passive"))
      (node (ref "EC1") (pin "46") (pinfunction "46_46") (pintype "passive"))
      (node (ref "EC1") (pin "47") (pinfunction "47_47") (pintype "passive"))
      (node (ref "EC1") (pin "65") (pinfunction "65_65") (pintype "passive"))
      (node (ref "EC1") (pin "7") (pinfunction "7_7") (pintype "passive"))
      (node (ref "EC1") (pin "83") (pinfunction "83_83") (pintype "passive"))
      (node (ref "EC1") (pin "97") (pinfunction "97_97") (pintype "passive"))
      (node (ref "EC2") (pin "135") (pinfunction "135_135") (pintype "passive"))
      (node (ref "EC2") (pin "157") (pinfunction "157_157") (pintype "passive"))
      (node (ref "EC2") (pin "179") (pinfunction "179_179") (pintype "passive"))
    )
    (net (code "208") (name "HSEC_5V0") (class "Default")
      (node (ref "EC1") (pin "112") (pinfunction "112_112") (pintype "passive"))
      (node (ref "EC1") (pin "48") (pinfunction "48_48") (pintype "passive"))
      (node (ref "EC1") (pin "84") (pinfunction "84_84") (pintype "passive"))
      (node (ref "EC1") (pin "98") (pinfunction "98_98") (pintype "passive"))
      (node (ref "EC2") (pin "158") (pinfunction "158_158") (pintype "passive"))
      (node (ref "EC2") (pin "180") (pinfunction "180_180") (pintype "passive"))
    )
    (net (code "209") (name "Net-(U1B-GPIO59)") (class "Default")
      (node (ref "R3") (pin "2") (pinfunction "2_2") (pintype "passive"))
      (node (ref "U1") (pin "M16") (pinfunction "GPIO59_M16") (pintype "bidirectional"))
    )
    (net (code "210") (name "Net-(U1B-GPIO61)") (class "Default")
      (node (ref "R4") (pin "2") (pinfunction "2_2") (pintype "passive"))
      (node (ref "U1") (pin "L16") (pinfunction "GPIO61_L16") (pintype "bidirectional"))
    )
    (net (code "211") (name "Net-(U1B-GPIO64)") (class "Default")
      (node (ref "R5") (pin "2") (pinfunction "2_2") (pintype "passive"))
      (node (ref "U1") (pin "L17") (pinfunction "GPIO64_L17") (pintype "bidirectional"))
    )
    (net (code "212") (name "Net-(U1B-GPIO66)") (class "Default")
      (node (ref "R6") (pin "2") (pinfunction "2_2") (pintype "passive"))
      (node (ref "U1") (pin "K17") (pinfunction "GPIO66_K17") (pintype "bidirectional"))
    )
    (net (code "213") (name "Net-(U1B-GPIO70)") (class "Default")
      (node (ref "R7") (pin "2") (pinfunction "2_2") (pintype "passive"))
      (node (ref "U1") (pin "A17") (pinfunction "GPIO70_A17") (pintype "bidirectional"))
    )
    (net (code "214") (name "Net-(U1B-GPIO72)") (class "Default")
      (node (ref "R8") (pin "2") (pinfunction "2_2") (pintype "passive"))
      (node (ref "U1") (pin "B16") (pinfunction "GPIO72_B16") (pintype "bidirectional"))
    )
    (net (code "215") (name "VDD_3V3") (class "Default")
      (node (ref "R1") (pin "2") (pinfunction "2_2") (pintype "passive"))
      (node (ref "R2") (pin "1") (pinfunction "1_1") (pintype "passive"))
    )
    (net (code "216") (name "unconnected-(EC1-Pad13)") (class "Default")
      (node (ref "EC1") (pin "13") (pinfunction "13_13") (pintype "passive+no_connect"))
    )
    (net (code "217") (name "unconnected-(EC1-Pad16)") (class "Default")
      (node (ref "EC1") (pin "16") (pinfunction "16_16") (pintype "passive+no_connect"))
    )
    (net (code "218") (name "unconnected-(EC1-Pad29)") (class "Default")
      (node (ref "EC1") (pin "29") (pinfunction "29_29") (pintype "passive+no_connect"))
    )
    (net (code "219") (name "unconnected-(EC1-Pad32)") (class "Default")
      (node (ref "EC1") (pin "32") (pinfunction "32_32") (pintype "passive+no_connect"))
    )
    (net (code "220") (name "unconnected-(EC1-Pad41)") (class "Default")
      (node (ref "EC1") (pin "41") (pinfunction "41_41") (pintype "passive+no_connect"))
    )
    (net (code "221") (name "unconnected-(EC1-Pad43)") (class "Default")
      (node (ref "EC1") (pin "43") (pinfunction "43_43") (pintype "passive+no_connect"))
    )
    (net (code "222") (name "unconnected-(EC1-Pad44)") (class "Default")
      (node (ref "EC1") (pin "44") (pinfunction "44_44") (pintype "passive+no_connect"))
    )
    (net (code "223") (name "unconnected-(EC1-Pad66)") (class "Default")
      (node (ref "EC1") (pin "66") (pinfunction "66_66") (pintype "passive+no_connect"))
    )
    (net (code "224") (name "unconnected-(EC1-Pad113)") (class "Default")
      (node (ref "EC1") (pin "113") (pinfunction "113_113") (pintype "passive+no_connect"))
    )
    (net (code "225") (name "unconnected-(EC1-Pad114)") (class "Default")
      (node (ref "EC1") (pin "114") (pinfunction "114_114") (pintype "passive+no_connect"))
    )
    (net (code "226") (name "unconnected-(EC1-Pad115)") (class "Default")
      (node (ref "EC1") (pin "115") (pinfunction "115_115") (pintype "passive+no_connect"))
    )
    (net (code "227") (name "unconnected-(EC1-Pad116)") (class "Default")
      (node (ref "EC1") (pin "116") (pinfunction "116_116") (pintype "passive+no_connect"))
    )
    (net (code "228") (name "unconnected-(EC1-Pad117)") (class "Default")
      (node (ref "EC1") (pin "117") (pinfunction "117_117") (pintype "passive+no_connect"))
    )
    (net (code "229") (name "unconnected-(EC1-Pad118)") (class "Default")
      (node (ref "EC1") (pin "118") (pinfunction "118_118") (pintype "passive+no_connect"))
    )
    (net (code "230") (name "unconnected-(EC1-Pad119)") (class "Default")
      (node (ref "EC1") (pin "119") (pinfunction "119_119") (pintype "passive+no_connect"))
    )
    (net (code "231") (name "unconnected-(EC2-Pad136)") (class "Default")
      (node (ref "EC2") (pin "136") (pinfunction "136_136") (pintype "passive+no_connect"))
    )
    (net (code "232") (name "unconnected-(EC2-Pad171)") (class "Default")
      (node (ref "EC2") (pin "171") (pinfunction "171_171") (pintype "passive+no_connect"))
    )
    (net (code "233") (name "unconnected-(EC2-Pad172)") (class "Default")
      (node (ref "EC2") (pin "172") (pinfunction "172_172") (pintype "passive+no_connect"))
    )
    (net (code "234") (name "unconnected-(EC2-Pad173)") (class "Default")
      (node (ref "EC2") (pin "173") (pinfunction "173_173") (pintype "passive+no_connect"))
    )
    (net (code "235") (name "unconnected-(EC2-Pad174)") (class "Default")
      (node (ref "EC2") (pin "174") (pinfunction "174_174") (pintype "passive+no_connect"))
    )
    (net (code "236") (name "unconnected-(EC2-Pad175)") (class "Default")
      (node (ref "EC2") (pin "175") (pinfunction "175_175") (pintype "passive+no_connect"))
    )
    (net (code "237") (name "unconnected-(EC2-Pad176)") (class "Default")
      (node (ref "EC2") (pin "176") (pinfunction "176_176") (pintype "passive+no_connect"))
    )
    (net (code "238") (name "unconnected-(EC2-Pad177)") (class "Default")
      (node (ref "EC2") (pin "177") (pinfunction "177_177") (pintype "passive+no_connect"))
    )
    (net (code "239") (name "unconnected-(EC2-Pad178)") (class "Default")
      (node (ref "EC2") (pin "178") (pinfunction "178_178") (pintype "passive+no_connect"))
    )
  )
)
